# POWERMANAGE2.net
KiCad netlist of a schematic drawn in Altium Designer
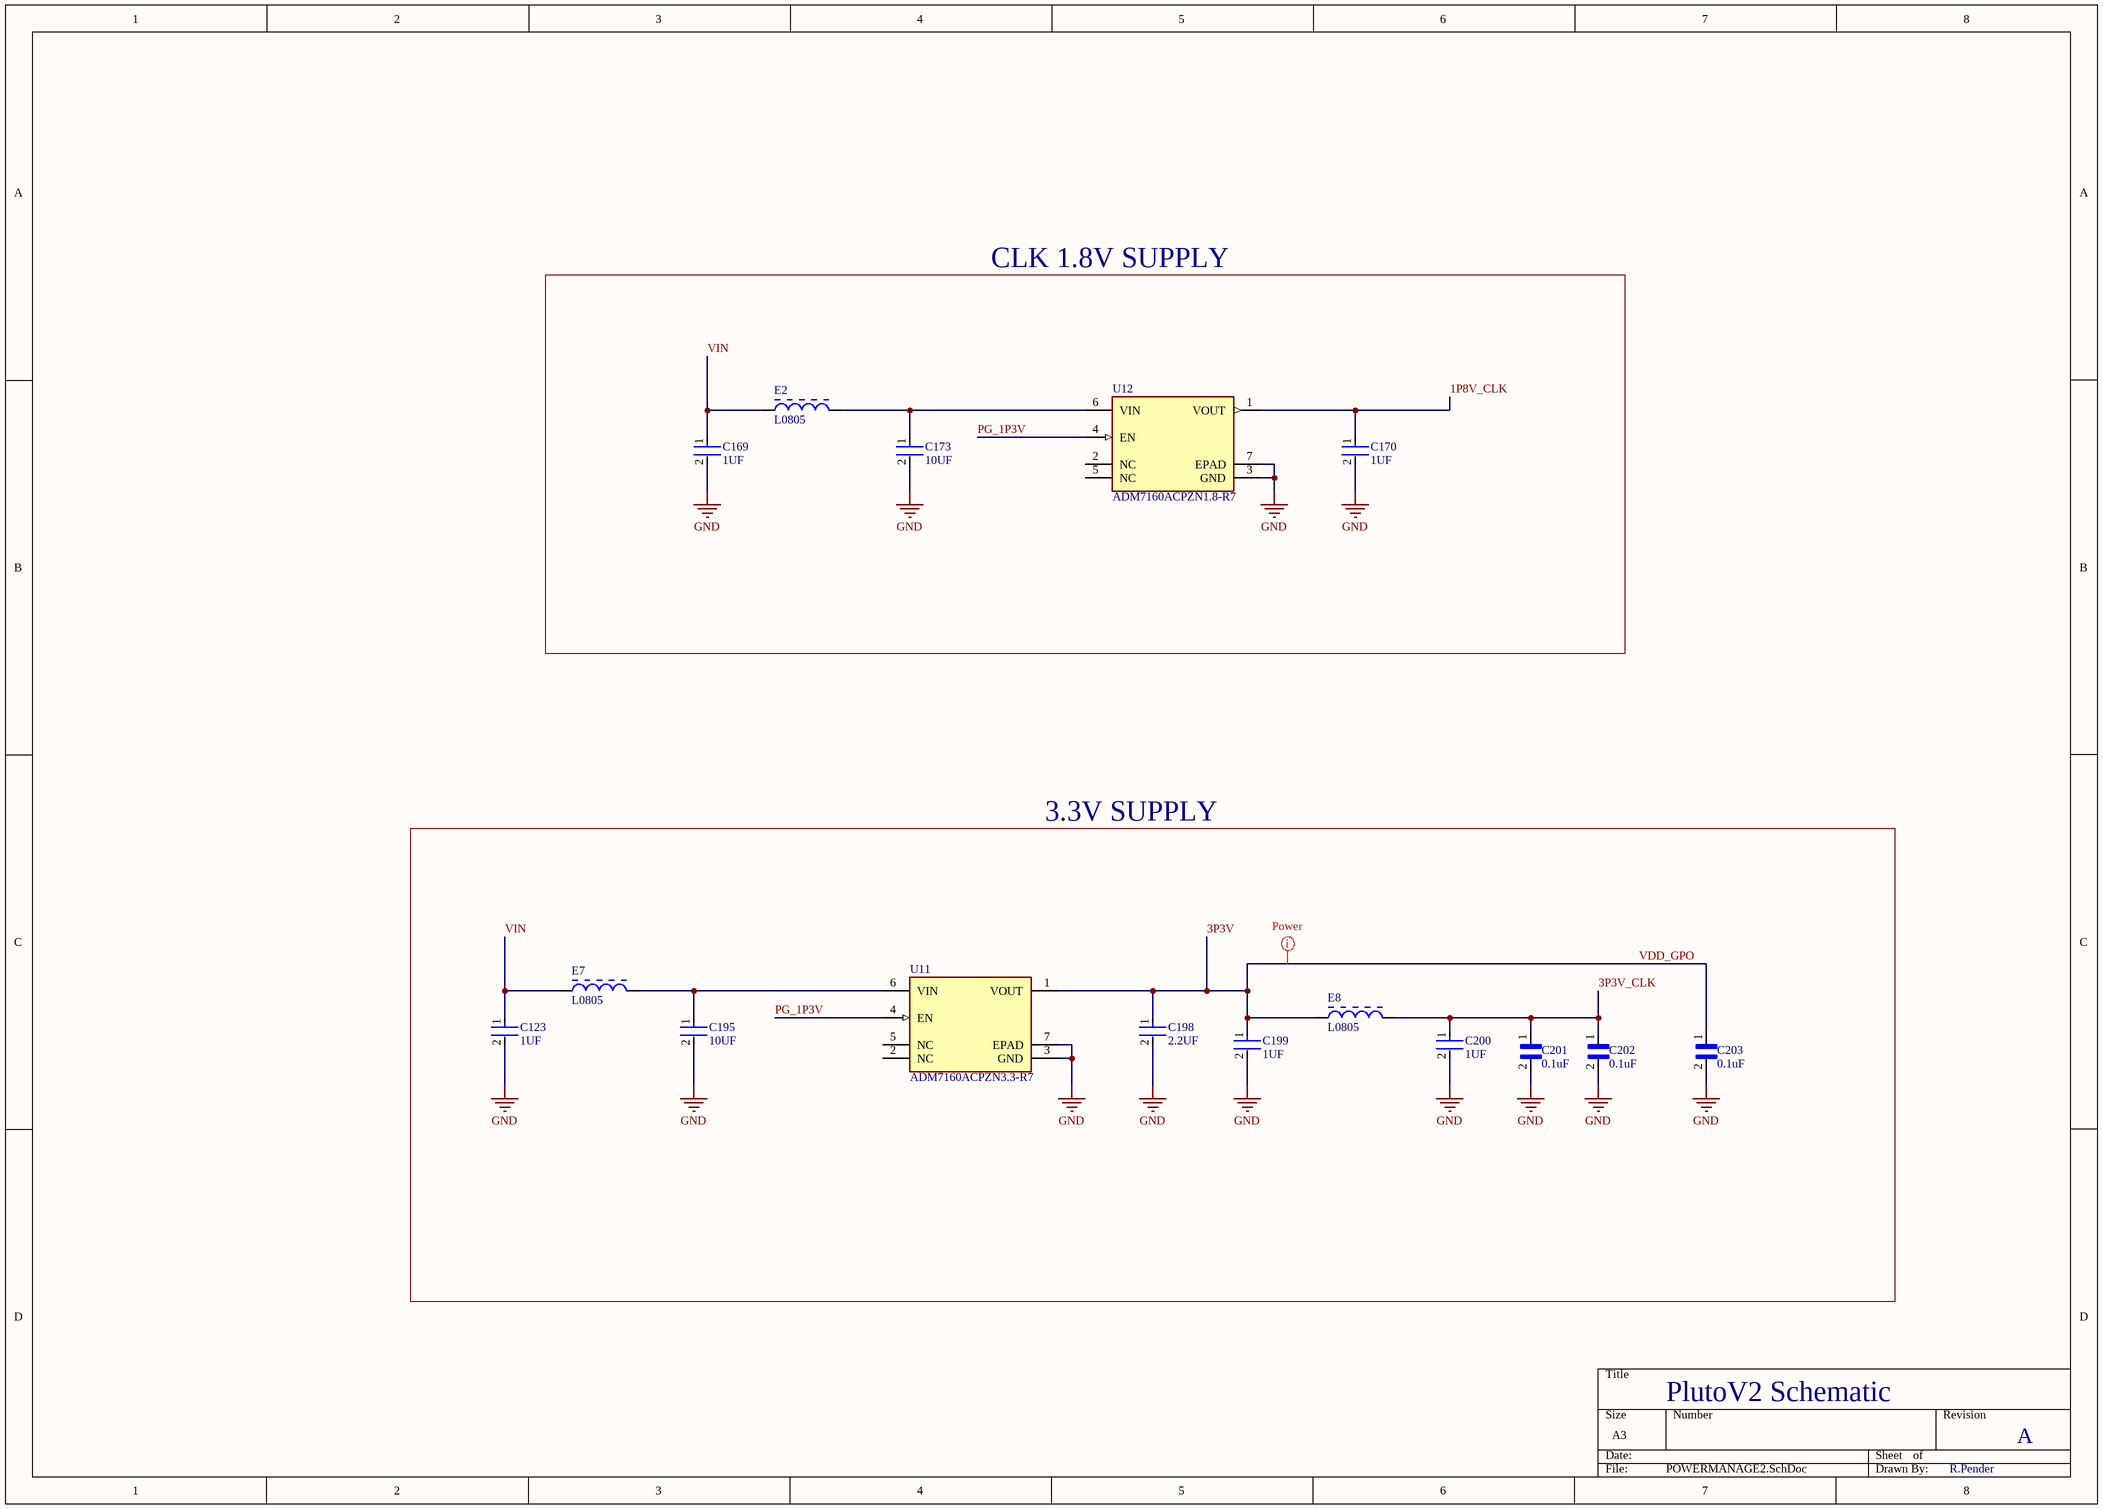
[diagram p0: POWERMANAGE2.SchDoc]

(export (version "E")
  (design (tool "Eeschema 10.0.6"))
  (components
    (comp (ref "C123")
      (value "1UF")
      (footprint "FP-0402-L_1_0_0_05-W_0_5-IPC_A")
      (description "None")
      (fields (field (name "TOLERANCE") "10%"))
      (libsource (lib "Altium Content Vault") (part "b4654b650e69147ec39a6b967a45e02"))
    )
    (comp (ref "C169")
      (value "1UF")
      (footprint "FP-0402-L_1_0_0_05-W_0_5-IPC_A")
      (description "None")
      (fields (field (name "TOLERANCE") "10%"))
      (libsource (lib "Altium Content Vault") (part "b4654b650e69147ec39a6b967a45e02"))
    )
    (comp (ref "C170")
      (value "1UF")
      (footprint "FP-0402-L_1_0_0_05-W_0_5-IPC_A")
      (description "None")
      (fields (field (name "TOLERANCE") "10%"))
      (libsource (lib "Altium Content Vault") (part "b4654b650e69147ec39a6b967a45e02"))
    )
    (comp (ref "C173")
      (value "10UF")
      (footprint "FP-GRM188-0_15-MFG")
      (description "Chip Multilayer Ceramic Capacitors for General Purpose, 0603, 10uF, X5R, 15%, 20%, 10V")
      (fields (field (name "TOLERANCE") "20%"))
      (libsource (lib "Altium Content Vault") (part "02cd4be3c70576c341d710602a673aa"))
    )
    (comp (ref "C195")
      (value "10UF")
      (footprint "FP-GRM188-0_15-MFG")
      (description "Chip Multilayer Ceramic Capacitors for General Purpose, 0603, 10uF, X5R, 15%, 20%, 10V")
      (fields (field (name "TOLERANCE") "20%"))
      (libsource (lib "Altium Content Vault") (part "02cd4be3c70576c341d710602a673aa"))
    )
    (comp (ref "C198")
      (value "2.2UF")
      (footprint "FP-GRM188-0_2-IPC_C")
      (description "Chip Multilayer Ceramic Capacitors for General Purpose, 0603, 2.2uF, X5R, 15%, 10%, 50V")
      (fields (field (name "TOLERANCE") "10%"))
      (libsource (lib "Altium Content Vault") (part "11868f565c42a9108669ba33697ecf6"))
    )
    (comp (ref "C199")
      (value "1UF")
      (footprint "FP-0402-L_1_0_0_05-W_0_5-IPC_A")
      (description "None")
      (fields (field (name "TOLERANCE") "10%"))
      (libsource (lib "Altium Content Vault") (part "b4654b650e69147ec39a6b967a45e02"))
    )
    (comp (ref "C200")
      (value "1UF")
      (footprint "FP-0402-L_1_0_0_05-W_0_5-IPC_A")
      (description "None")
      (fields (field (name "TOLERANCE") "10%"))
      (libsource (lib "Altium Content Vault") (part "b4654b650e69147ec39a6b967a45e02"))
    )
    (comp (ref "C201")
      (value "0.1uF")
      (footprint "CAPC0603X33N")
      (description "CAP 0.1UF 16VDC X5R 20% SMD 0201 PAPER TAPE")
      (fields (field (name "MP") "GRM033R61C104ME84D"))
      (libsource (lib "GRM033R61C104ME84D") (part "GRM033R61C104ME84D"))
    )
    (comp (ref "C202")
      (value "0.1uF")
      (footprint "CAPC0603X33N")
      (description "CAP 0.1UF 16VDC X5R 20% SMD 0201 PAPER TAPE")
      (fields (field (name "MP") "GRM033R61C104ME84D"))
      (libsource (lib "GRM033R61C104ME84D") (part "GRM033R61C104ME84D"))
    )
    (comp (ref "C203")
      (value "0.1uF")
      (footprint "CAPC0603X33N")
      (description "CAP 0.1UF 16VDC X5R 20% SMD 0201 PAPER TAPE")
      (fields (field (name "MP") "GRM033R61C104ME84D"))
      (libsource (lib "GRM033R61C104ME84D") (part "GRM033R61C104ME84D"))
    )
    (comp (ref "E2")
      (value "L0805")
      (footprint "TDK-MPZ2012S101A-2_V")
      (fields (field (name "TOLERANCE") "25%") (field (name "MANUFACTURER") "TDK"))
      (libsource (lib "Altium Content Vault") (part "BEAD-2"))
    )
    (comp (ref "E7")
      (value "L0805")
      (footprint "TDK-MPZ2012S101A-2_V")
      (fields (field (name "TOLERANCE") "25%") (field (name "MANUFACTURER") "TDK"))
      (libsource (lib "Altium Content Vault") (part "BEAD-2"))
    )
    (comp (ref "E8")
      (value "L0805")
      (footprint "TDK-MPZ2012S101A-2_V")
      (fields (field (name "TOLERANCE") "25%") (field (name "MANUFACTURER") "TDK"))
      (libsource (lib "Altium Content Vault") (part "BEAD-2"))
    )
    (comp (ref "U11")
      (value "ADM7160ACPZN3.3-R7")
      (footprint "FP-CP-6-3-IPC_A")
      (description "IC REG LINEAR 3.3V 200MA 6LFCSP")
      (libsource (lib "Altium Content Vault") (part "1bcd84081306a58d9bf24361e4fa6b1"))
    )
    (comp (ref "U12")
      (value "ADM7160ACPZN1.8-R7")
      (footprint "FP-CP-6-3-IPC_C")
      (description "IC REG LINEAR 1.8V 200MA 6LFCSP")
      (libsource (lib "Altium Content Vault") (part "4c8513698d558cca4e2e33da6060110"))
    )
  )
  (nets
    (net (code "1") (name "/1P8V_CLK") (class "Default")
      (node (ref "C170") (pin "1") (pinfunction "1_1") (pintype "passive"))
      (node (ref "U12") (pin "1") (pinfunction "VOUT_1") (pintype "output"))
    )
    (net (code "2") (name "/3P3V") (class "Default")
      (node (ref "C198") (pin "1") (pinfunction "1_1") (pintype "passive"))
      (node (ref "C199") (pin "1") (pinfunction "1_1") (pintype "passive"))
      (node (ref "C203") (pin "1") (pinfunction "1_1") (pintype "passive"))
      (node (ref "E8") (pin "1") (pinfunction "1_1") (pintype "passive"))
      (node (ref "U11") (pin "1") (pinfunction "VOUT_1") (pintype "power_in"))
    )
    (net (code "3") (name "/3P3V_CLK") (class "Default")
      (node (ref "C200") (pin "1") (pinfunction "1_1") (pintype "passive"))
      (node (ref "C201") (pin "1") (pinfunction "1_1") (pintype "passive"))
      (node (ref "C202") (pin "1") (pinfunction "1_1") (pintype "passive"))
      (node (ref "E8") (pin "2") (pinfunction "2_2") (pintype "passive"))
    )
    (net (code "4") (name "/PG_1P3V") (class "Default")
      (node (ref "U11") (pin "4") (pinfunction "EN_4") (pintype "input"))
      (node (ref "U12") (pin "4") (pinfunction "EN_4") (pintype "input"))
    )
    (net (code "5") (name "/VIN") (class "Default")
      (node (ref "C123") (pin "1") (pinfunction "1_1") (pintype "passive"))
      (node (ref "C169") (pin "1") (pinfunction "1_1") (pintype "passive"))
      (node (ref "E2") (pin "1") (pinfunction "1_1") (pintype "passive"))
      (node (ref "E7") (pin "1") (pinfunction "1_1") (pintype "passive"))
    )
    (net (code "6") (name "GND") (class "Default")
      (node (ref "C123") (pin "2") (pinfunction "2_2") (pintype "passive"))
      (node (ref "C169") (pin "2") (pinfunction "2_2") (pintype "passive"))
      (node (ref "C170") (pin "2") (pinfunction "2_2") (pintype "passive"))
      (node (ref "C173") (pin "2") (pinfunction "2_2") (pintype "passive"))
      (node (ref "C195") (pin "2") (pinfunction "2_2") (pintype "passive"))
      (node (ref "C198") (pin "2") (pinfunction "2_2") (pintype "passive"))
      (node (ref "C199") (pin "2") (pinfunction "2_2") (pintype "passive"))
      (node (ref "C200") (pin "2") (pinfunction "2_2") (pintype "passive"))
      (node (ref "C201") (pin "2") (pinfunction "2_2") (pintype "passive"))
      (node (ref "C202") (pin "2") (pinfunction "2_2") (pintype "passive"))
      (node (ref "C203") (pin "2") (pinfunction "2_2") (pintype "passive"))
      (node (ref "U11") (pin "3") (pinfunction "GND_3") (pintype "power_in"))
      (node (ref "U11") (pin "7") (pinfunction "EPAD_7") (pintype "power_in"))
      (node (ref "U12") (pin "3") (pinfunction "GND_3") (pintype "power_in"))
      (node (ref "U12") (pin "7") (pinfunction "EPAD_7") (pintype "passive"))
    )
    (net (code "7") (name "Net-(U11-VIN)") (class "Default")
      (node (ref "C195") (pin "1") (pinfunction "1_1") (pintype "passive"))
      (node (ref "E7") (pin "2") (pinfunction "2_2") (pintype "passive"))
      (node (ref "U11") (pin "6") (pinfunction "VIN_6") (pintype "power_in"))
    )
    (net (code "8") (name "Net-(U12-VIN)") (class "Default")
      (node (ref "C173") (pin "1") (pinfunction "1_1") (pintype "passive"))
      (node (ref "E2") (pin "2") (pinfunction "2_2") (pintype "passive"))
      (node (ref "U12") (pin "6") (pinfunction "VIN_6") (pintype "power_in"))
    )
    (net (code "9") (name "unconnected-(U11-NC-Pad2)") (class "Default")
      (node (ref "U11") (pin "2") (pinfunction "NC_2") (pintype "passive"))
    )
    (net (code "10") (name "unconnected-(U11-NC-Pad5)") (class "Default")
      (node (ref "U11") (pin "5") (pinfunction "NC_5") (pintype "passive"))
    )
    (net (code "11") (name "unconnected-(U12-NC-Pad2)") (class "Default")
      (node (ref "U12") (pin "2") (pinfunction "NC_2") (pintype "passive"))
    )
    (net (code "12") (name "unconnected-(U12-NC-Pad5)") (class "Default")
      (node (ref "U12") (pin "5") (pinfunction "NC_5") (pintype "passive"))
    )
  )
)
